# Spannungsversorgung.net
KiCad netlist of a schematic drawn in Altium Designer
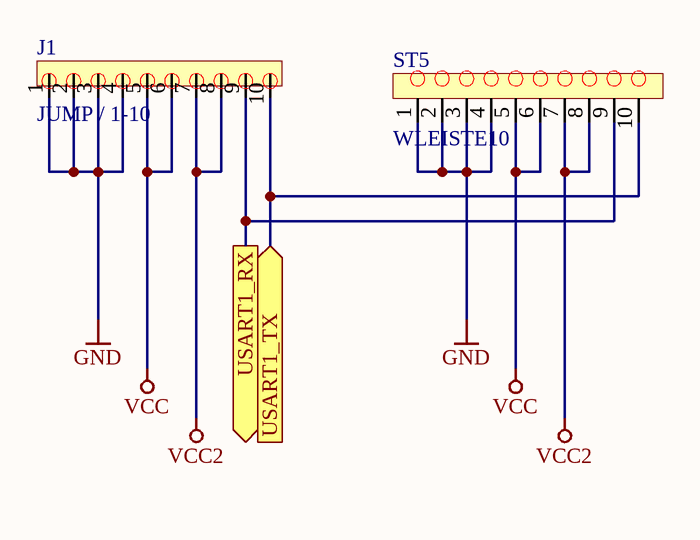
[diagram p0: Spannungsversorgung.SchDoc]

(export (version "E")
  (design (tool "Eeschema 10.0.6"))
  (components
    (comp (ref "J1")
      (value "JUMP / 1-10")
      (footprint "JUMPER1/10")
      (description "Stiftleiste 10polig RM2,54")
      (libsource (lib "Steckverbinder") (part "JUMP / 1-10"))
    )
    (comp (ref "ST5")
      (value "WLEISTE10")
      (footprint "WLEISTE10_GERADE")
      (description "Wannenleiste 10polig")
      (libsource (lib "Steckverbinder") (part "WLEISTE10"))
    )
  )
  (nets
    (net (code "1") (name "/USART1_RX") (class "Default")
      (node (ref "J1") (pin "9") (pinfunction "9_9") (pintype "passive"))
      (node (ref "ST5") (pin "9") (pinfunction "9_9") (pintype "passive"))
    )
    (net (code "2") (name "/USART1_TX") (class "Default")
      (node (ref "J1") (pin "10") (pinfunction "10_10") (pintype "passive"))
      (node (ref "ST5") (pin "10") (pinfunction "10_10") (pintype "passive"))
    )
    (net (code "3") (name "GND") (class "Default")
      (node (ref "J1") (pin "1") (pinfunction "1_1") (pintype "passive"))
      (node (ref "J1") (pin "2") (pinfunction "2_2") (pintype "passive"))
      (node (ref "J1") (pin "3") (pinfunction "3_3") (pintype "passive"))
      (node (ref "J1") (pin "4") (pinfunction "4_4") (pintype "passive"))
      (node (ref "ST5") (pin "1") (pinfunction "1_1") (pintype "passive"))
      (node (ref "ST5") (pin "2") (pinfunction "2_2") (pintype "passive"))
      (node (ref "ST5") (pin "3") (pinfunction "3_3") (pintype "passive"))
      (node (ref "ST5") (pin "4") (pinfunction "4_4") (pintype "passive"))
    )
    (net (code "4") (name "VCC") (class "Default")
      (node (ref "J1") (pin "5") (pinfunction "5_5") (pintype "passive"))
      (node (ref "J1") (pin "6") (pinfunction "6_6") (pintype "passive"))
      (node (ref "ST5") (pin "5") (pinfunction "5_5") (pintype "passive"))
      (node (ref "ST5") (pin "6") (pinfunction "6_6") (pintype "passive"))
    )
    (net (code "5") (name "VCC2") (class "Default")
      (node (ref "J1") (pin "7") (pinfunction "7_7") (pintype "passive"))
      (node (ref "J1") (pin "8") (pinfunction "8_8") (pintype "passive"))
      (node (ref "ST5") (pin "7") (pinfunction "7_7") (pintype "passive"))
      (node (ref "ST5") (pin "8") (pinfunction "8_8") (pintype "passive"))
    )
  )
)
